# converter.net
KiCad netlist of a schematic drawn in EAGLE
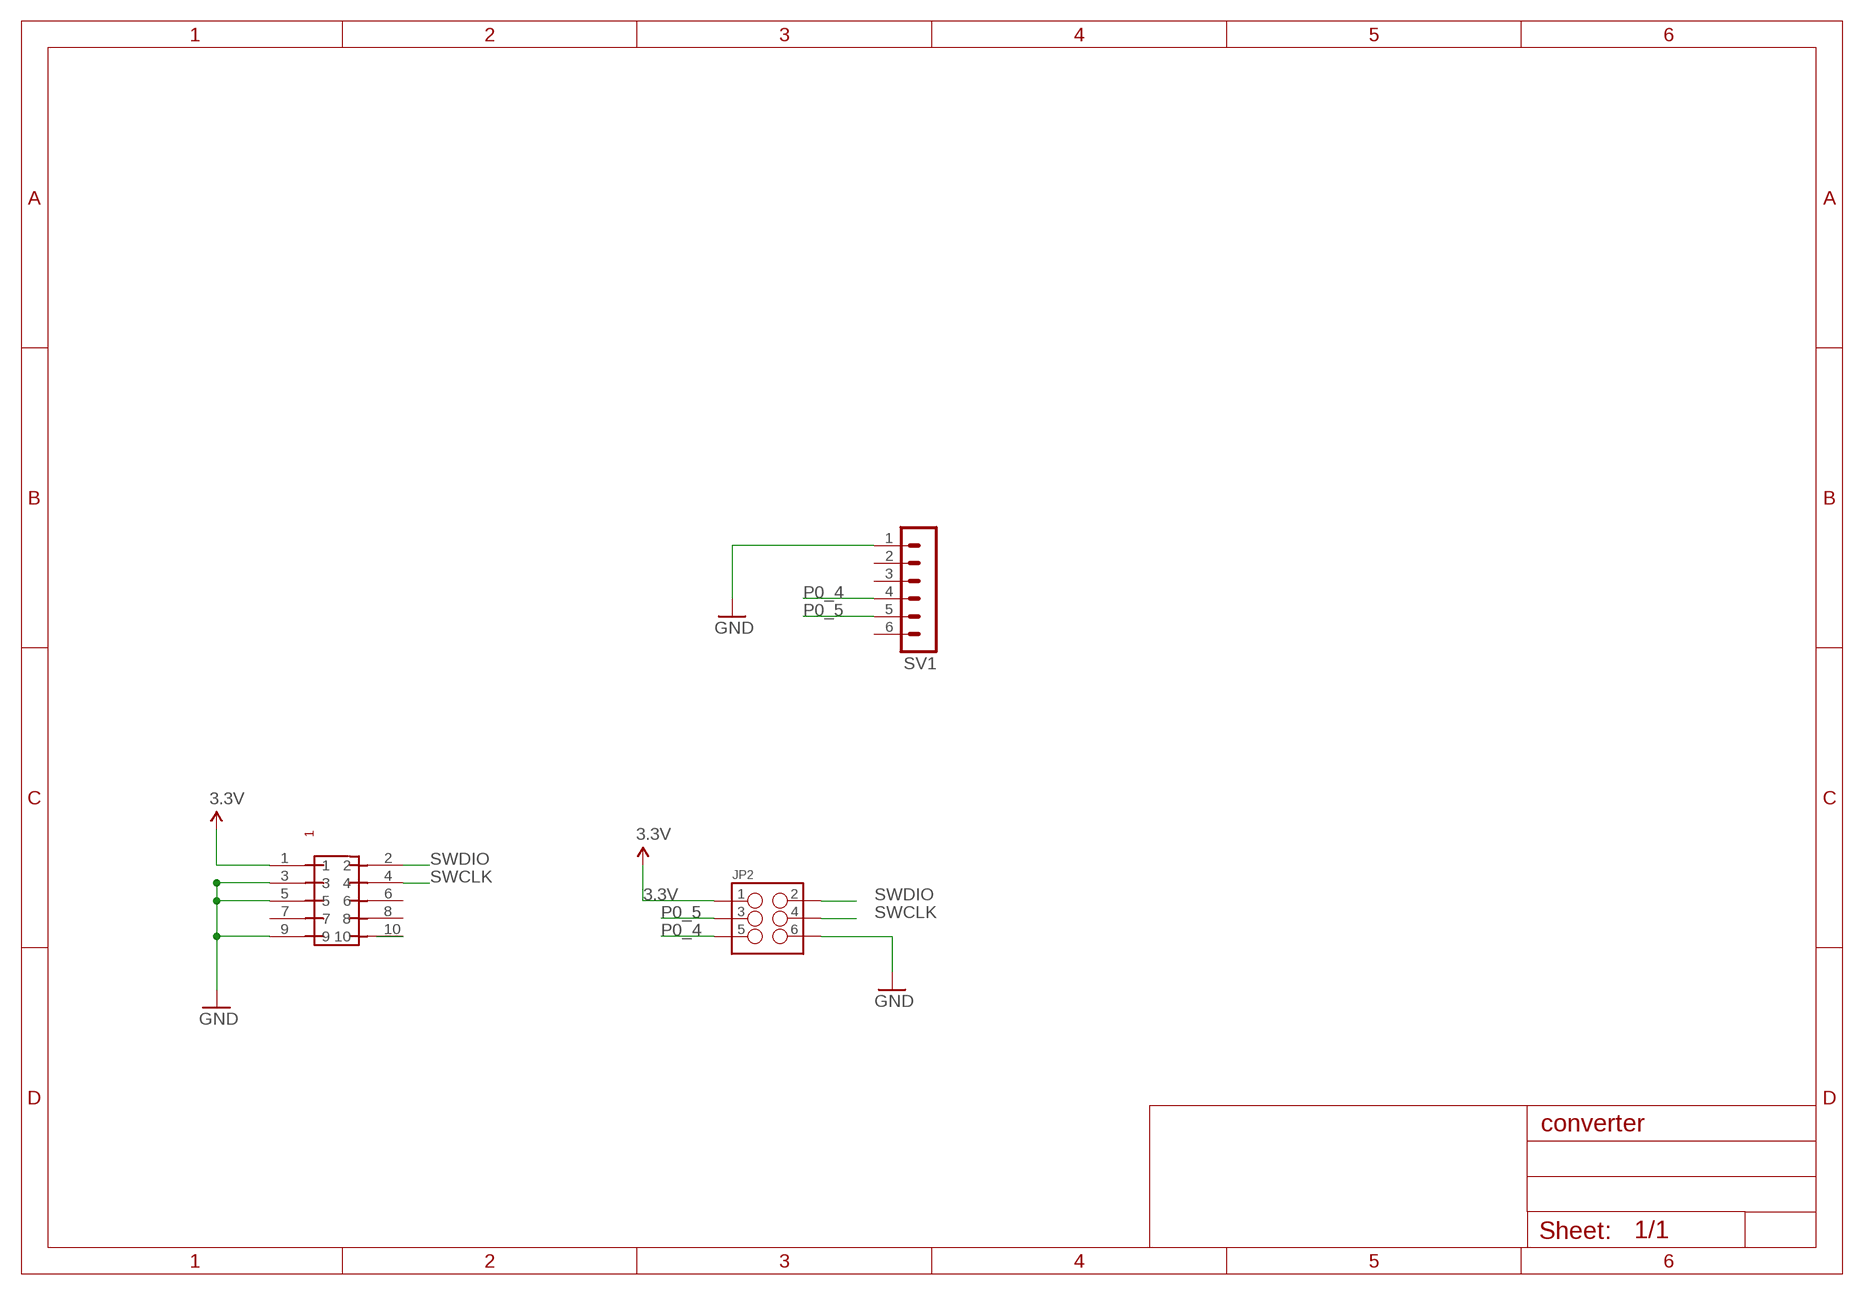
[diagram p0: schematic, sheet 1]

(export (version "E")
  (design (tool "Eeschema 10.0.6"))
  (components
    (comp (ref "JP2")
      (value "M03X2")
      (footprint "eagle-import:2X3-SHROUDED")
      (libsource (lib "eagle-import") (part "M03X2"))
    )
    (comp (ref "SV1")
      (value "MA06-1")
      (footprint "eagle-import:MA06-1")
      (libsource (lib "eagle-import") (part "MA06-1"))
    )
    (comp (ref "U$5")
      (value "PIN-HEADER-SMT(1.27MM)2X5")
      (footprint "eagle-import:PIN-HEADER-SMT(1.27MM)2X5")
      (libsource (lib "eagle-import") (part "PIN-HEADER-SMT(1.27MM)2X5"))
    )
  )
  (nets
    (net (code "1") (name "/P0_4") (class "Default")
      (node (ref "JP2") (pin "5") (pinfunction "5_5") (pintype "bidirectional"))
      (node (ref "SV1") (pin "4") (pinfunction "4_4") (pintype "passive"))
    )
    (net (code "2") (name "/P0_5") (class "Default")
      (node (ref "JP2") (pin "3") (pinfunction "3_3") (pintype "bidirectional"))
      (node (ref "SV1") (pin "5") (pinfunction "5_5") (pintype "passive"))
    )
    (net (code "3") (name "/SWCLK") (class "Default")
      (node (ref "JP2") (pin "4") (pinfunction "4_4") (pintype "bidirectional"))
      (node (ref "U$5") (pin "4") (pinfunction "4_4") (pintype "bidirectional"))
    )
    (net (code "4") (name "/SWDIO") (class "Default")
      (node (ref "JP2") (pin "2") (pinfunction "2_2") (pintype "bidirectional"))
      (node (ref "U$5") (pin "2") (pinfunction "2_2") (pintype "bidirectional"))
    )
    (net (code "5") (name "3.3V") (class "Default")
      (node (ref "JP2") (pin "1") (pinfunction "1_1") (pintype "bidirectional"))
      (node (ref "U$5") (pin "1") (pinfunction "1_1") (pintype "bidirectional"))
    )
    (net (code "6") (name "GND") (class "Default")
      (node (ref "JP2") (pin "6") (pinfunction "6_6") (pintype "bidirectional"))
      (node (ref "SV1") (pin "1") (pinfunction "1_1") (pintype "passive"))
      (node (ref "U$5") (pin "3") (pinfunction "3_3") (pintype "bidirectional"))
      (node (ref "U$5") (pin "5") (pinfunction "5_5") (pintype "bidirectional"))
      (node (ref "U$5") (pin "9") (pinfunction "9_9") (pintype "bidirectional"))
    )
    (net (code "7") (name "unconnected-(SV1-Pad2)") (class "Default")
      (node (ref "SV1") (pin "2") (pinfunction "2_2") (pintype "passive"))
    )
    (net (code "8") (name "unconnected-(SV1-Pad3)") (class "Default")
      (node (ref "SV1") (pin "3") (pinfunction "3_3") (pintype "passive"))
    )
    (net (code "9") (name "unconnected-(SV1-Pad6)") (class "Default")
      (node (ref "SV1") (pin "6") (pinfunction "6_6") (pintype "passive"))
    )
    (net (code "10") (name "unconnected-(U$5-Pad6)") (class "Default")
      (node (ref "U$5") (pin "6") (pinfunction "6_6") (pintype "bidirectional"))
    )
    (net (code "11") (name "unconnected-(U$5-Pad7)") (class "Default")
      (node (ref "U$5") (pin "7") (pinfunction "7_7") (pintype "bidirectional"))
    )
    (net (code "12") (name "unconnected-(U$5-Pad8)") (class "Default")
      (node (ref "U$5") (pin "8") (pinfunction "8_8") (pintype "bidirectional"))
    )
    (net (code "13") (name "unconnected-(U$5-Pad10)") (class "Default")
      (node (ref "U$5") (pin "10") (pinfunction "10_10") (pintype "bidirectional"))
    )
  )
)
